# Sample_FPC_FFC_TestBoard.net
KiCad netlist of a schematic drawn in Altium Designer
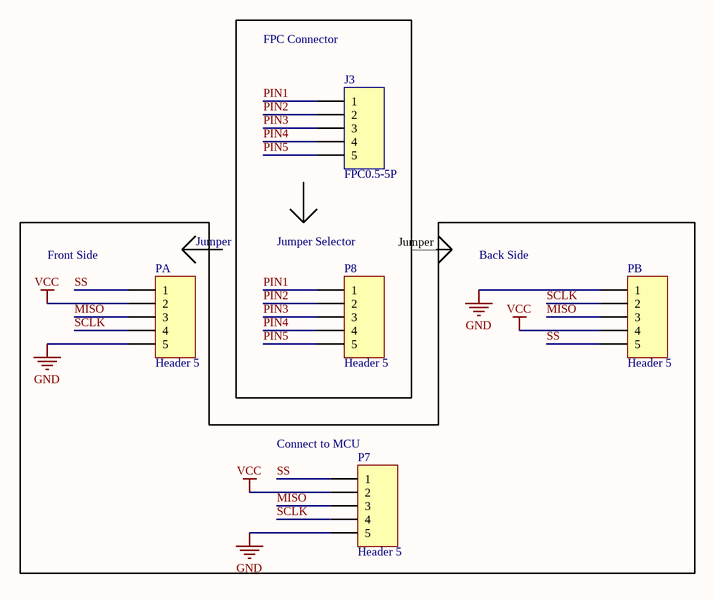
[diagram p0: Sample_FPC_FFC_TestBoard.SchDoc]

(export (version "E")
  (design (tool "Eeschema 10.0.6"))
  (components
    (comp (ref "J3")
      (value "FPC0.5-5P")
      (footprint "FPC0.5-5P")
      (libsource (lib "FMA_Sensor") (part "FPC0.5-5P"))
    )
    (comp (ref "P7")
      (value "Header 5")
      (footprint "HDR1X5")
      (description "Header, 4-Pin")
      (fields (field (name "PUBLISHER") "Altium Limited"))
      (libsource (lib "FMA_Sensor") (part "Header 5"))
    )
    (comp (ref "P8")
      (value "Header 5")
      (footprint "HDR1X5-2")
      (description "Header, 4-Pin")
      (fields (field (name "PUBLISHER") "Altium Limited"))
      (libsource (lib "FMA_Sensor") (part "Header 5"))
    )
    (comp (ref "PA")
      (value "Header 5")
      (footprint "HDR1X5-2")
      (description "Header, 4-Pin")
      (fields (field (name "PUBLISHER") "Altium Limited"))
      (libsource (lib "FMA_Sensor") (part "Header 5"))
    )
    (comp (ref "PB")
      (value "Header 5")
      (footprint "HDR1X5-2")
      (description "Header, 4-Pin")
      (fields (field (name "PUBLISHER") "Altium Limited"))
      (libsource (lib "FMA_Sensor") (part "Header 5"))
    )
  )
  (nets
    (net (code "1") (name "/MISO") (class "Default")
      (node (ref "P7") (pin "3") (pinfunction "3_3") (pintype "passive"))
      (node (ref "PA") (pin "3") (pinfunction "3_3") (pintype "passive"))
      (node (ref "PB") (pin "3") (pinfunction "3_3") (pintype "passive"))
    )
    (net (code "2") (name "/PIN1") (class "Default")
      (node (ref "J3") (pin "1") (pinfunction "1_1") (pintype "passive"))
      (node (ref "P8") (pin "1") (pinfunction "1_1") (pintype "passive"))
    )
    (net (code "3") (name "/PIN2") (class "Default")
      (node (ref "J3") (pin "2") (pinfunction "2_2") (pintype "passive"))
      (node (ref "P8") (pin "2") (pinfunction "2_2") (pintype "passive"))
    )
    (net (code "4") (name "/PIN3") (class "Default")
      (node (ref "J3") (pin "3") (pinfunction "3_3") (pintype "passive"))
      (node (ref "P8") (pin "3") (pinfunction "3_3") (pintype "passive"))
    )
    (net (code "5") (name "/PIN4") (class "Default")
      (node (ref "J3") (pin "4") (pinfunction "4_4") (pintype "passive"))
      (node (ref "P8") (pin "4") (pinfunction "4_4") (pintype "passive"))
    )
    (net (code "6") (name "/PIN5") (class "Default")
      (node (ref "J3") (pin "5") (pinfunction "5_5") (pintype "passive"))
      (node (ref "P8") (pin "5") (pinfunction "5_5") (pintype "passive"))
    )
    (net (code "7") (name "/SCLK") (class "Default")
      (node (ref "P7") (pin "4") (pinfunction "4_4") (pintype "passive"))
      (node (ref "PA") (pin "4") (pinfunction "4_4") (pintype "passive"))
      (node (ref "PB") (pin "2") (pinfunction "2_2") (pintype "passive"))
    )
    (net (code "8") (name "/SS") (class "Default")
      (node (ref "P7") (pin "1") (pinfunction "1_1") (pintype "passive"))
      (node (ref "PA") (pin "1") (pinfunction "1_1") (pintype "passive"))
      (node (ref "PB") (pin "5") (pinfunction "5_5") (pintype "passive"))
    )
    (net (code "9") (name "GND") (class "Default")
      (node (ref "P7") (pin "5") (pinfunction "5_5") (pintype "passive"))
      (node (ref "PA") (pin "5") (pinfunction "5_5") (pintype "passive"))
      (node (ref "PB") (pin "1") (pinfunction "1_1") (pintype "passive"))
    )
    (net (code "10") (name "VCC") (class "Default")
      (node (ref "P7") (pin "2") (pinfunction "2_2") (pintype "passive"))
      (node (ref "PA") (pin "2") (pinfunction "2_2") (pintype "passive"))
      (node (ref "PB") (pin "4") (pinfunction "4_4") (pintype "passive"))
    )
  )
)
